# vixen1.net
KiCad netlist of a schematic drawn in EAGLE
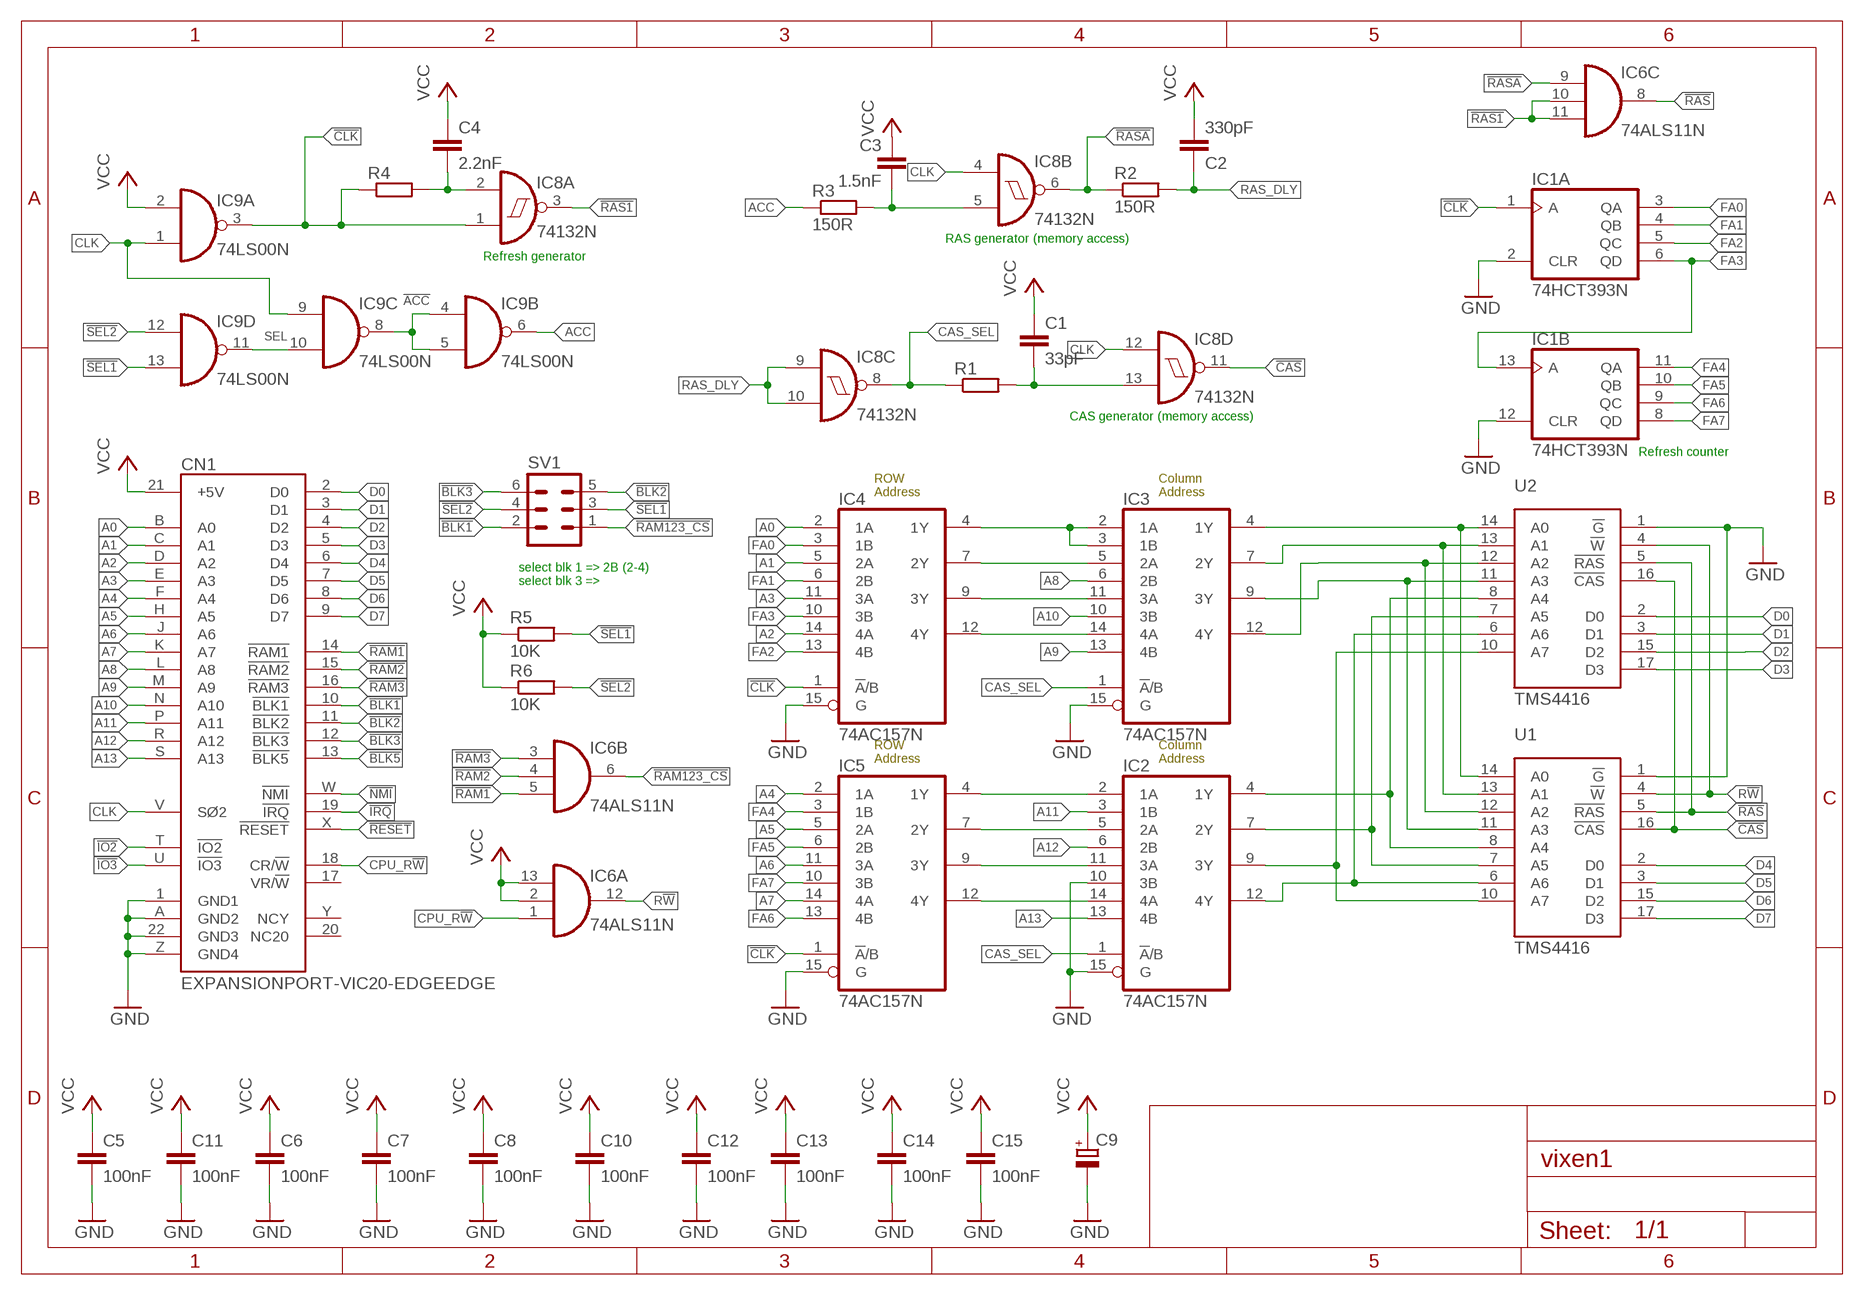
[diagram p0: schematic, sheet 1]

(export (version "E")
  (design (tool "Eeschema 10.0.6"))
  (components
    (comp (ref "C1")
      (value "33pF")
      (footprint "eagle-import:C025-025X050")
      (libsource (lib "eagle-import") (part "C-EU025-025X050"))
    )
    (comp (ref "C2")
      (value "330pF")
      (footprint "eagle-import:C025-025X050")
      (libsource (lib "eagle-import") (part "C-EU025-025X050"))
    )
    (comp (ref "C3")
      (value "1.5nF")
      (footprint "eagle-import:C025-025X050")
      (libsource (lib "eagle-import") (part "C-EU025-025X050"))
    )
    (comp (ref "C4")
      (value "2.2nF")
      (footprint "eagle-import:C025-025X050")
      (libsource (lib "eagle-import") (part "C-EU025-025X050"))
    )
    (comp (ref "C5")
      (value "100nF")
      (footprint "eagle-import:C025-025X050")
      (libsource (lib "eagle-import") (part "C-EU025-025X050"))
    )
    (comp (ref "C6")
      (value "100nF")
      (footprint "eagle-import:C025-025X050")
      (libsource (lib "eagle-import") (part "C-EU025-025X050"))
    )
    (comp (ref "C7")
      (value "100nF")
      (footprint "eagle-import:C025-025X050")
      (libsource (lib "eagle-import") (part "C-EU025-025X050"))
    )
    (comp (ref "C8")
      (value "100nF")
      (footprint "eagle-import:C025-025X050")
      (libsource (lib "eagle-import") (part "C-EU025-025X050"))
    )
    (comp (ref "C9")
      (value "CPOL-EUE15-5AXIAL")
      (footprint "eagle-import:E15-5")
      (libsource (lib "eagle-import") (part "CPOL-EUE15-5AXIAL"))
    )
    (comp (ref "C10")
      (value "100nF")
      (footprint "eagle-import:C025-025X050")
      (libsource (lib "eagle-import") (part "C-EU025-025X050"))
    )
    (comp (ref "C11")
      (value "100nF")
      (footprint "eagle-import:C025-025X050")
      (libsource (lib "eagle-import") (part "C-EU025-025X050"))
    )
    (comp (ref "C12")
      (value "100nF")
      (footprint "eagle-import:C025-025X050")
      (libsource (lib "eagle-import") (part "C-EU025-025X050"))
    )
    (comp (ref "C13")
      (value "100nF")
      (footprint "eagle-import:C025-025X050")
      (libsource (lib "eagle-import") (part "C-EU025-025X050"))
    )
    (comp (ref "C14")
      (value "100nF")
      (footprint "eagle-import:C025-025X050")
      (libsource (lib "eagle-import") (part "C-EU025-025X050"))
    )
    (comp (ref "C15")
      (value "100nF")
      (footprint "eagle-import:C025-025X050")
      (libsource (lib "eagle-import") (part "C-EU025-025X050"))
    )
    (comp (ref "CN1")
      (value "EXPANSIONPORT-VIC20-EDGEEDGE")
      (footprint "eagle-import:UPS44EDGE")
      (libsource (lib "eagle-import") (part "EXPANSIONPORT-VIC20-EDGEEDGE"))
    )
    (comp (ref "IC1")
      (value "74HCT393N")
      (footprint "eagle-import:DIL14")
      (libsource (lib "eagle-import") (part "74393NHCT"))
    )
    (comp (ref "IC2")
      (value "74AC157N")
      (footprint "eagle-import:DIL16")
      (libsource (lib "eagle-import") (part "74157NAC"))
    )
    (comp (ref "IC3")
      (value "74AC157N")
      (footprint "eagle-import:DIL16")
      (libsource (lib "eagle-import") (part "74157NAC"))
    )
    (comp (ref "IC4")
      (value "74AC157N")
      (footprint "eagle-import:DIL16")
      (libsource (lib "eagle-import") (part "74157NAC"))
    )
    (comp (ref "IC5")
      (value "74AC157N")
      (footprint "eagle-import:DIL16")
      (libsource (lib "eagle-import") (part "74157NAC"))
    )
    (comp (ref "IC6")
      (value "74ALS11N")
      (footprint "eagle-import:DIL14")
      (libsource (lib "eagle-import") (part "7411NALS"))
    )
    (comp (ref "IC8")
      (value "74132N")
      (footprint "eagle-import:DIL14")
      (libsource (lib "eagle-import") (part "74132N"))
    )
    (comp (ref "IC9")
      (value "74LS00N")
      (footprint "eagle-import:DIL14")
      (libsource (lib "eagle-import") (part "7400NLS"))
    )
    (comp (ref "R1")
      (value "R-EU_0204/7")
      (footprint "eagle-import:0204_7")
      (libsource (lib "eagle-import") (part "R-EU_0204/7"))
    )
    (comp (ref "R2")
      (value "150R")
      (footprint "eagle-import:0204_7")
      (libsource (lib "eagle-import") (part "R-EU_0204/7"))
    )
    (comp (ref "R3")
      (value "150R")
      (footprint "eagle-import:0204_7")
      (libsource (lib "eagle-import") (part "R-EU_0204/7"))
    )
    (comp (ref "R4")
      (value "R-EU_0204/7")
      (footprint "eagle-import:0204_7")
      (libsource (lib "eagle-import") (part "R-EU_0204/7"))
    )
    (comp (ref "R5")
      (value "10K")
      (footprint "eagle-import:0204_7")
      (libsource (lib "eagle-import") (part "R-EU_0204/7"))
    )
    (comp (ref "R6")
      (value "10K")
      (footprint "eagle-import:0204_7")
      (libsource (lib "eagle-import") (part "R-EU_0204/7"))
    )
    (comp (ref "SV1")
      (value "MA03-2")
      (footprint "eagle-import:MA03-2")
      (libsource (lib "eagle-import") (part "MA03-2"))
    )
    (comp (ref "U1")
      (value "TMS4416")
      (footprint "eagle-import:DIL18")
      (libsource (lib "eagle-import") (part "TMS4416"))
    )
    (comp (ref "U2")
      (value "TMS4416")
      (footprint "eagle-import:DIL18")
      (libsource (lib "eagle-import") (part "TMS4416"))
    )
  )
  (nets
    (net (code "1") (name "/CPU_R~{W}") (class "Default")
      (node (ref "CN1") (pin "18") (pinfunction "CR/~{W}_18") (pintype "output"))
      (node (ref "IC6") (pin "1") (pinfunction "I0_1") (pintype "input"))
    )
    (net (code "2") (name "/R~{W}") (class "Default")
      (node (ref "IC6") (pin "12") (pinfunction "O_12") (pintype "output"))
      (node (ref "U1") (pin "4") (pinfunction "~{W}_4") (pintype "bidirectional"))
      (node (ref "U2") (pin "4") (pinfunction "~{W}_4") (pintype "bidirectional"))
    )
    (net (code "3") (name "/SEL") (class "Default")
      (node (ref "IC9") (pin "10") (pinfunction "I1_10") (pintype "input"))
      (node (ref "IC9") (pin "11") (pinfunction "O_11") (pintype "output"))
    )
    (net (code "4") (name "/~{ACC}") (class "Default")
      (node (ref "IC9") (pin "4") (pinfunction "I0_4") (pintype "input"))
      (node (ref "IC9") (pin "5") (pinfunction "I1_5") (pintype "input"))
      (node (ref "IC9") (pin "8") (pinfunction "O_8") (pintype "output"))
    )
    (net (code "5") (name "/~{BLK1}") (class "Default")
      (node (ref "CN1") (pin "10") (pinfunction "~{BLK1}_10") (pintype "output"))
      (node (ref "SV1") (pin "2") (pinfunction "2_2") (pintype "passive"))
    )
    (net (code "6") (name "/~{BLK2}") (class "Default")
      (node (ref "CN1") (pin "11") (pinfunction "~{BLK2}_11") (pintype "output"))
      (node (ref "SV1") (pin "5") (pinfunction "5_5") (pintype "passive"))
    )
    (net (code "7") (name "/~{BLK3}") (class "Default")
      (node (ref "CN1") (pin "12") (pinfunction "~{BLK3}_12") (pintype "output"))
      (node (ref "SV1") (pin "6") (pinfunction "6_6") (pintype "passive"))
    )
    (net (code "8") (name "/~{BLK5}") (class "Default")
      (node (ref "CN1") (pin "13") (pinfunction "~{BLK5}_13") (pintype "output"))
    )
    (net (code "9") (name "/~{CAS}") (class "Default")
      (node (ref "IC8") (pin "11") (pinfunction "O_11") (pintype "output"))
      (node (ref "U1") (pin "16") (pinfunction "~{CAS}_16") (pintype "bidirectional"))
      (node (ref "U2") (pin "16") (pinfunction "~{CAS}_16") (pintype "bidirectional"))
    )
    (net (code "10") (name "/~{CLK}") (class "Default")
      (node (ref "IC1") (pin "1") (pinfunction "A_1") (pintype "input"))
      (node (ref "IC4") (pin "1") (pinfunction "~{A}/B_1") (pintype "input"))
      (node (ref "IC5") (pin "1") (pinfunction "~{A}/B_1") (pintype "input"))
      (node (ref "IC8") (pin "1") (pinfunction "I0_1") (pintype "input"))
      (node (ref "IC9") (pin "3") (pinfunction "O_3") (pintype "output"))
      (node (ref "R4") (pin "1") (pinfunction "1_1") (pintype "passive"))
    )
    (net (code "11") (name "/~{IO2}") (class "Default")
      (node (ref "CN1") (pin "T") (pinfunction "~{IO2}_T") (pintype "output"))
    )
    (net (code "12") (name "/~{IO3}") (class "Default")
      (node (ref "CN1") (pin "U") (pinfunction "~{IO3}_U") (pintype "output"))
    )
    (net (code "13") (name "/~{IRQ}") (class "Default")
      (node (ref "CN1") (pin "19") (pinfunction "~{IRQ}_19") (pintype "bidirectional"))
    )
    (net (code "14") (name "/~{NMI}") (class "Default")
      (node (ref "CN1") (pin "W") (pinfunction "~{NMI}_W") (pintype "bidirectional"))
    )
    (net (code "15") (name "/~{RAM1}") (class "Default")
      (node (ref "CN1") (pin "14") (pinfunction "~{RAM1}_14") (pintype "output"))
      (node (ref "IC6") (pin "5") (pinfunction "I2_5") (pintype "input"))
    )
    (net (code "16") (name "/~{RAM2}") (class "Default")
      (node (ref "CN1") (pin "15") (pinfunction "~{RAM2}_15") (pintype "output"))
      (node (ref "IC6") (pin "4") (pinfunction "I1_4") (pintype "input"))
    )
    (net (code "17") (name "/~{RAM3}") (class "Default")
      (node (ref "CN1") (pin "16") (pinfunction "~{RAM3}_16") (pintype "output"))
      (node (ref "IC6") (pin "3") (pinfunction "I0_3") (pintype "input"))
    )
    (net (code "18") (name "/~{RAM123_CS}") (class "Default")
      (node (ref "IC6") (pin "6") (pinfunction "O_6") (pintype "output"))
      (node (ref "SV1") (pin "1") (pinfunction "1_1") (pintype "passive"))
    )
    (net (code "19") (name "/~{RAS1}") (class "Default")
      (node (ref "IC6") (pin "10") (pinfunction "I1_10") (pintype "input"))
      (node (ref "IC6") (pin "11") (pinfunction "I2_11") (pintype "input"))
      (node (ref "IC8") (pin "3") (pinfunction "O_3") (pintype "output"))
    )
    (net (code "20") (name "/~{RASA}") (class "Default")
      (node (ref "IC6") (pin "9") (pinfunction "I0_9") (pintype "input"))
      (node (ref "IC8") (pin "6") (pinfunction "O_6") (pintype "output"))
      (node (ref "R2") (pin "1") (pinfunction "1_1") (pintype "passive"))
    )
    (net (code "21") (name "/~{RAS}") (class "Default")
      (node (ref "IC6") (pin "8") (pinfunction "O_8") (pintype "output"))
      (node (ref "U1") (pin "5") (pinfunction "~{RAS}_5") (pintype "bidirectional"))
      (node (ref "U2") (pin "5") (pinfunction "~{RAS}_5") (pintype "bidirectional"))
    )
    (net (code "22") (name "/~{RESET}") (class "Default")
      (node (ref "CN1") (pin "X") (pinfunction "~{RESET}_X") (pintype "bidirectional"))
    )
    (net (code "23") (name "/~{SEL1}") (class "Default")
      (node (ref "IC9") (pin "13") (pinfunction "I1_13") (pintype "input"))
      (node (ref "R5") (pin "2") (pinfunction "2_2") (pintype "passive"))
      (node (ref "SV1") (pin "3") (pinfunction "3_3") (pintype "passive"))
    )
    (net (code "24") (name "/~{SEL2}") (class "Default")
      (node (ref "IC9") (pin "12") (pinfunction "I0_12") (pintype "input"))
      (node (ref "R6") (pin "2") (pinfunction "2_2") (pintype "passive"))
      (node (ref "SV1") (pin "4") (pinfunction "4_4") (pintype "passive"))
    )
    (net (code "25") (name "A0") (class "Default")
      (node (ref "CN1") (pin "B") (pinfunction "A0_B") (pintype "output"))
      (node (ref "IC4") (pin "2") (pinfunction "1A_2") (pintype "input"))
    )
    (net (code "26") (name "A1") (class "Default")
      (node (ref "CN1") (pin "C") (pinfunction "A1_C") (pintype "output"))
      (node (ref "IC4") (pin "5") (pinfunction "2A_5") (pintype "input"))
    )
    (net (code "27") (name "A2") (class "Default")
      (node (ref "CN1") (pin "D") (pinfunction "A2_D") (pintype "output"))
      (node (ref "IC4") (pin "14") (pinfunction "4A_14") (pintype "input"))
    )
    (net (code "28") (name "A3") (class "Default")
      (node (ref "CN1") (pin "E") (pinfunction "A3_E") (pintype "output"))
      (node (ref "IC4") (pin "11") (pinfunction "3A_11") (pintype "input"))
    )
    (net (code "29") (name "A4") (class "Default")
      (node (ref "CN1") (pin "F") (pinfunction "A4_F") (pintype "output"))
      (node (ref "IC5") (pin "2") (pinfunction "1A_2") (pintype "input"))
    )
    (net (code "30") (name "A5") (class "Default")
      (node (ref "CN1") (pin "H") (pinfunction "A5_H") (pintype "output"))
      (node (ref "IC5") (pin "5") (pinfunction "2A_5") (pintype "input"))
    )
    (net (code "31") (name "A6") (class "Default")
      (node (ref "CN1") (pin "J") (pinfunction "A6_J") (pintype "output"))
      (node (ref "IC5") (pin "11") (pinfunction "3A_11") (pintype "input"))
    )
    (net (code "32") (name "A7") (class "Default")
      (node (ref "CN1") (pin "K") (pinfunction "A7_K") (pintype "output"))
      (node (ref "IC5") (pin "14") (pinfunction "4A_14") (pintype "input"))
    )
    (net (code "33") (name "A8") (class "Default")
      (node (ref "CN1") (pin "L") (pinfunction "A8_L") (pintype "output"))
      (node (ref "IC3") (pin "6") (pinfunction "2B_6") (pintype "input"))
    )
    (net (code "34") (name "A9") (class "Default")
      (node (ref "CN1") (pin "M") (pinfunction "A9_M") (pintype "output"))
      (node (ref "IC3") (pin "13") (pinfunction "4B_13") (pintype "input"))
    )
    (net (code "35") (name "A10") (class "Default")
      (node (ref "CN1") (pin "N") (pinfunction "A10_N") (pintype "output"))
      (node (ref "IC3") (pin "10") (pinfunction "3B_10") (pintype "input"))
    )
    (net (code "36") (name "A11") (class "Default")
      (node (ref "CN1") (pin "P") (pinfunction "A11_P") (pintype "output"))
      (node (ref "IC2") (pin "3") (pinfunction "1B_3") (pintype "input"))
    )
    (net (code "37") (name "A12") (class "Default")
      (node (ref "CN1") (pin "R") (pinfunction "A12_R") (pintype "output"))
      (node (ref "IC2") (pin "6") (pinfunction "2B_6") (pintype "input"))
    )
    (net (code "38") (name "A13") (class "Default")
      (node (ref "CN1") (pin "S") (pinfunction "A13_S") (pintype "output"))
      (node (ref "IC2") (pin "13") (pinfunction "4B_13") (pintype "input"))
    )
    (net (code "39") (name "ACC") (class "Default")
      (node (ref "IC9") (pin "6") (pinfunction "O_6") (pintype "output"))
      (node (ref "R3") (pin "1") (pinfunction "1_1") (pintype "passive"))
    )
    (net (code "40") (name "CAS_SEL") (class "Default")
      (node (ref "IC2") (pin "1") (pinfunction "~{A}/B_1") (pintype "input"))
      (node (ref "IC3") (pin "1") (pinfunction "~{A}/B_1") (pintype "input"))
      (node (ref "IC8") (pin "8") (pinfunction "O_8") (pintype "output"))
      (node (ref "R1") (pin "1") (pinfunction "1_1") (pintype "passive"))
    )
    (net (code "41") (name "CLK") (class "Default")
      (node (ref "CN1") (pin "V") (pinfunction "SØ2_V") (pintype "output"))
      (node (ref "IC8") (pin "12") (pinfunction "I0_12") (pintype "input"))
      (node (ref "IC8") (pin "4") (pinfunction "I0_4") (pintype "input"))
      (node (ref "IC9") (pin "1") (pinfunction "I0_1") (pintype "input"))
      (node (ref "IC9") (pin "9") (pinfunction "I0_9") (pintype "input"))
    )
    (net (code "42") (name "D0") (class "Default")
      (node (ref "CN1") (pin "2") (pinfunction "D0_2") (pintype "bidirectional"))
      (node (ref "U2") (pin "2") (pinfunction "D0_2") (pintype "bidirectional"))
    )
    (net (code "43") (name "D1") (class "Default")
      (node (ref "CN1") (pin "3") (pinfunction "D1_3") (pintype "bidirectional"))
      (node (ref "U2") (pin "3") (pinfunction "D1_3") (pintype "bidirectional"))
    )
    (net (code "44") (name "D2") (class "Default")
      (node (ref "CN1") (pin "4") (pinfunction "D2_4") (pintype "bidirectional"))
      (node (ref "U2") (pin "15") (pinfunction "D2_15") (pintype "bidirectional"))
    )
    (net (code "45") (name "D3") (class "Default")
      (node (ref "CN1") (pin "5") (pinfunction "D3_5") (pintype "bidirectional"))
      (node (ref "U2") (pin "17") (pinfunction "D3_17") (pintype "bidirectional"))
    )
    (net (code "46") (name "D4") (class "Default")
      (node (ref "CN1") (pin "6") (pinfunction "D4_6") (pintype "bidirectional"))
      (node (ref "U1") (pin "2") (pinfunction "D0_2") (pintype "bidirectional"))
    )
    (net (code "47") (name "D5") (class "Default")
      (node (ref "CN1") (pin "7") (pinfunction "D5_7") (pintype "bidirectional"))
      (node (ref "U1") (pin "3") (pinfunction "D1_3") (pintype "bidirectional"))
    )
    (net (code "48") (name "D6") (class "Default")
      (node (ref "CN1") (pin "8") (pinfunction "D6_8") (pintype "bidirectional"))
      (node (ref "U1") (pin "15") (pinfunction "D2_15") (pintype "bidirectional"))
    )
    (net (code "49") (name "D7") (class "Default")
      (node (ref "CN1") (pin "9") (pinfunction "D7_9") (pintype "bidirectional"))
      (node (ref "U1") (pin "17") (pinfunction "D3_17") (pintype "bidirectional"))
    )
    (net (code "50") (name "FA0") (class "Default")
      (node (ref "IC1") (pin "3") (pinfunction "QA_3") (pintype "output"))
      (node (ref "IC4") (pin "3") (pinfunction "1B_3") (pintype "input"))
    )
    (net (code "51") (name "FA1") (class "Default")
      (node (ref "IC1") (pin "4") (pinfunction "QB_4") (pintype "output"))
      (node (ref "IC4") (pin "6") (pinfunction "2B_6") (pintype "input"))
    )
    (net (code "52") (name "FA2") (class "Default")
      (node (ref "IC1") (pin "5") (pinfunction "QC_5") (pintype "output"))
      (node (ref "IC4") (pin "13") (pinfunction "4B_13") (pintype "input"))
    )
    (net (code "53") (name "FA3") (class "Default")
      (node (ref "IC1") (pin "13") (pinfunction "A_13") (pintype "input"))
      (node (ref "IC1") (pin "6") (pinfunction "QD_6") (pintype "output"))
      (node (ref "IC4") (pin "10") (pinfunction "3B_10") (pintype "input"))
    )
    (net (code "54") (name "FA4") (class "Default")
      (node (ref "IC1") (pin "11") (pinfunction "QA_11") (pintype "output"))
      (node (ref "IC5") (pin "3") (pinfunction "1B_3") (pintype "input"))
    )
    (net (code "55") (name "FA5") (class "Default")
      (node (ref "IC1") (pin "10") (pinfunction "QB_10") (pintype "output"))
      (node (ref "IC5") (pin "6") (pinfunction "2B_6") (pintype "input"))
    )
    (net (code "56") (name "FA6") (class "Default")
      (node (ref "IC1") (pin "9") (pinfunction "QC_9") (pintype "output"))
      (node (ref "IC5") (pin "13") (pinfunction "4B_13") (pintype "input"))
    )
    (net (code "57") (name "FA7") (class "Default")
      (node (ref "IC1") (pin "8") (pinfunction "QD_8") (pintype "output"))
      (node (ref "IC5") (pin "10") (pinfunction "3B_10") (pintype "input"))
    )
    (net (code "58") (name "GND") (class "Default")
      (node (ref "C10") (pin "2") (pinfunction "2_2") (pintype "passive"))
      (node (ref "C11") (pin "2") (pinfunction "2_2") (pintype "passive"))
      (node (ref "C12") (pin "2") (pinfunction "2_2") (pintype "passive"))
      (node (ref "C13") (pin "2") (pinfunction "2_2") (pintype "passive"))
      (node (ref "C14") (pin "2") (pinfunction "2_2") (pintype "passive"))
      (node (ref "C15") (pin "2") (pinfunction "2_2") (pintype "passive"))
      (node (ref "C5") (pin "2") (pinfunction "2_2") (pintype "passive"))
      (node (ref "C6") (pin "2") (pinfunction "2_2") (pintype "passive"))
      (node (ref "C7") (pin "2") (pinfunction "2_2") (pintype "passive"))
      (node (ref "C8") (pin "2") (pinfunction "2_2") (pintype "passive"))
      (node (ref "C9") (pin "-") (pinfunction "-_-") (pintype "passive"))
      (node (ref "CN1") (pin "1") (pinfunction "GND1_1") (pintype "passive"))
      (node (ref "CN1") (pin "22") (pinfunction "GND3_22") (pintype "passive"))
      (node (ref "CN1") (pin "A") (pinfunction "GND2_A") (pintype "passive"))
      (node (ref "CN1") (pin "Z") (pinfunction "GND4_Z") (pintype "passive"))
      (node (ref "IC1") (pin "12") (pinfunction "CLR_12") (pintype "input"))
      (node (ref "IC1") (pin "2") (pinfunction "CLR_2") (pintype "input"))
      (node (ref "IC2") (pin "10") (pinfunction "3B_10") (pintype "input"))
      (node (ref "IC2") (pin "15") (pinfunction "G_15") (pintype "input"))
      (node (ref "IC3") (pin "15") (pinfunction "G_15") (pintype "input"))
      (node (ref "IC4") (pin "15") (pinfunction "G_15") (pintype "input"))
      (node (ref "IC5") (pin "15") (pinfunction "G_15") (pintype "input"))
      (node (ref "U1") (pin "1") (pinfunction "~{G}_1") (pintype "bidirectional"))
      (node (ref "U2") (pin "1") (pinfunction "~{G}_1") (pintype "bidirectional"))
    )
    (net (code "59") (name "Net-(IC2A-1A)") (class "Default")
      (node (ref "IC2") (pin "2") (pinfunction "1A_2") (pintype "input"))
      (node (ref "IC5") (pin "4") (pinfunction "1Y_4") (pintype "output"))
    )
    (net (code "60") (name "Net-(IC2A-1Y)") (class "Default")
      (node (ref "IC2") (pin "4") (pinfunction "1Y_4") (pintype "output"))
      (node (ref "U1") (pin "8") (pinfunction "A4_8") (pintype "input"))
      (node (ref "U2") (pin "8") (pinfunction "A4_8") (pintype "input"))
    )
    (net (code "61") (name "Net-(IC2A-2A)") (class "Default")
      (node (ref "IC2") (pin "5") (pinfunction "2A_5") (pintype "input"))
      (node (ref "IC5") (pin "7") (pinfunction "2Y_7") (pintype "output"))
    )
    (net (code "62") (name "Net-(IC2A-2Y)") (class "Default")
      (node (ref "IC2") (pin "7") (pinfunction "2Y_7") (pintype "output"))
      (node (ref "U1") (pin "7") (pinfunction "A5_7") (pintype "input"))
      (node (ref "U2") (pin "7") (pinfunction "A5_7") (pintype "input"))
    )
    (net (code "63") (name "Net-(IC2A-3A)") (class "Default")
      (node (ref "IC2") (pin "11") (pinfunction "3A_11") (pintype "input"))
      (node (ref "IC5") (pin "9") (pinfunction "3Y_9") (pintype "output"))
    )
    (net (code "64") (name "Net-(IC2A-3Y)") (class "Default")
      (node (ref "IC2") (pin "9") (pinfunction "3Y_9") (pintype "output"))
      (node (ref "U1") (pin "10") (pinfunction "A7_10") (pintype "input"))
      (node (ref "U2") (pin "10") (pinfunction "A7_10") (pintype "input"))
    )
    (net (code "65") (name "Net-(IC2A-4A)") (class "Default")
      (node (ref "IC2") (pin "14") (pinfunction "4A_14") (pintype "input"))
      (node (ref "IC5") (pin "12") (pinfunction "4Y_12") (pintype "output"))
    )
    (net (code "66") (name "Net-(IC2A-4Y)") (class "Default")
      (node (ref "IC2") (pin "12") (pinfunction "4Y_12") (pintype "output"))
      (node (ref "U1") (pin "6") (pinfunction "A6_6") (pintype "input"))
      (node (ref "U2") (pin "6") (pinfunction "A6_6") (pintype "input"))
    )
    (net (code "67") (name "Net-(IC3A-1A)") (class "Default")
      (node (ref "IC3") (pin "2") (pinfunction "1A_2") (pintype "input"))
      (node (ref "IC3") (pin "3") (pinfunction "1B_3") (pintype "input"))
      (node (ref "IC4") (pin "4") (pinfunction "1Y_4") (pintype "output"))
    )
    (net (code "68") (name "Net-(IC3A-1Y)") (class "Default")
      (node (ref "IC3") (pin "4") (pinfunction "1Y_4") (pintype "output"))
      (node (ref "U1") (pin "14") (pinfunction "A0_14") (pintype "input"))
      (node (ref "U2") (pin "14") (pinfunction "A0_14") (pintype "input"))
    )
    (net (code "69") (name "Net-(IC3A-2A)") (class "Default")
      (node (ref "IC3") (pin "5") (pinfunction "2A_5") (pintype "input"))
      (node (ref "IC4") (pin "7") (pinfunction "2Y_7") (pintype "output"))
    )
    (net (code "70") (name "Net-(IC3A-2Y)") (class "Default")
      (node (ref "IC3") (pin "7") (pinfunction "2Y_7") (pintype "output"))
      (node (ref "U1") (pin "13") (pinfunction "A1_13") (pintype "input"))
      (node (ref "U2") (pin "13") (pinfunction "A1_13") (pintype "input"))
    )
    (net (code "71") (name "Net-(IC3A-3A)") (class "Default")
      (node (ref "IC3") (pin "11") (pinfunction "3A_11") (pintype "input"))
      (node (ref "IC4") (pin "9") (pinfunction "3Y_9") (pintype "output"))
    )
    (net (code "72") (name "Net-(IC3A-3Y)") (class "Default")
      (node (ref "IC3") (pin "9") (pinfunction "3Y_9") (pintype "output"))
      (node (ref "U1") (pin "11") (pinfunction "A3_11") (pintype "input"))
      (node (ref "U2") (pin "11") (pinfunction "A3_11") (pintype "input"))
    )
    (net (code "73") (name "Net-(IC3A-4A)") (class "Default")
      (node (ref "IC3") (pin "14") (pinfunction "4A_14") (pintype "input"))
      (node (ref "IC4") (pin "12") (pinfunction "4Y_12") (pintype "output"))
    )
    (net (code "74") (name "Net-(IC3A-4Y)") (class "Default")
      (node (ref "IC3") (pin "12") (pinfunction "4Y_12") (pintype "output"))
      (node (ref "U1") (pin "12") (pinfunction "A2_12") (pintype "input"))
      (node (ref "U2") (pin "12") (pinfunction "A2_12") (pintype "input"))
    )
    (net (code "75") (name "Net-(IC8A-I1)") (class "Default")
      (node (ref "C4") (pin "2") (pinfunction "2_2") (pintype "passive"))
      (node (ref "IC8") (pin "2") (pinfunction "I1_2") (pintype "input"))
      (node (ref "R4") (pin "2") (pinfunction "2_2") (pintype "passive"))
    )
    (net (code "76") (name "Net-(IC8B-I1)") (class "Default")
      (node (ref "C3") (pin "2") (pinfunction "2_2") (pintype "passive"))
      (node (ref "IC8") (pin "5") (pinfunction "I1_5") (pintype "input"))
      (node (ref "R3") (pin "2") (pinfunction "2_2") (pintype "passive"))
    )
    (net (code "77") (name "Net-(IC8D-I1)") (class "Default")
      (node (ref "C1") (pin "2") (pinfunction "2_2") (pintype "passive"))
      (node (ref "IC8") (pin "13") (pinfunction "I1_13") (pintype "input"))
      (node (ref "R1") (pin "2") (pinfunction "2_2") (pintype "passive"))
    )
    (net (code "78") (name "RAS_DLY") (class "Default")
      (node (ref "C2") (pin "1") (pinfunction "1_1") (pintype "passive"))
      (node (ref "IC8") (pin "10") (pinfunction "I1_10") (pintype "input"))
      (node (ref "IC8") (pin "9") (pinfunction "I0_9") (pintype "input"))
      (node (ref "R2") (pin "2") (pinfunction "2_2") (pintype "passive"))
    )
    (net (code "79") (name "VCC") (class "Default")
      (node (ref "C1") (pin "1") (pinfunction "1_1") (pintype "passive"))
      (node (ref "C10") (pin "1") (pinfunction "1_1") (pintype "passive"))
      (node (ref "C11") (pin "1") (pinfunction "1_1") (pintype "passive"))
      (node (ref "C12") (pin "1") (pinfunction "1_1") (pintype "passive"))
      (node (ref "C13") (pin "1") (pinfunction "1_1") (pintype "passive"))
      (node (ref "C14") (pin "1") (pinfunction "1_1") (pintype "passive"))
      (node (ref "C15") (pin "1") (pinfunction "1_1") (pintype "passive"))
      (node (ref "C2") (pin "2") (pinfunction "2_2") (pintype "passive"))
      (node (ref "C3") (pin "1") (pinfunction "1_1") (pintype "passive"))
      (node (ref "C4") (pin "1") (pinfunction "1_1") (pintype "passive"))
      (node (ref "C5") (pin "1") (pinfunction "1_1") (pintype "passive"))
      (node (ref "C6") (pin "1") (pinfunction "1_1") (pintype "passive"))
      (node (ref "C7") (pin "1") (pinfunction "1_1") (pintype "passive"))
      (node (ref "C8") (pin "1") (pinfunction "1_1") (pintype "passive"))
      (node (ref "C9") (pin "+") (pinfunction "+_+") (pintype "passive"))
      (node (ref "CN1") (pin "21") (pinfunction "+5V_21") (pintype "power_in"))
      (node (ref "IC6") (pin "13") (pinfunction "I2_13") (pintype "input"))
      (node (ref "IC6") (pin "2") (pinfunction "I1_2") (pintype "input"))
      (node (ref "IC9") (pin "2") (pinfunction "I1_2") (pintype "input"))
      (node (ref "R5") (pin "1") (pinfunction "1_1") (pintype "passive"))
      (node (ref "R6") (pin "1") (pinfunction "1_1") (pintype "passive"))
    )
    (net (code "80") (name "unconnected-(CN1-NC20-Pad20)") (class "Default")
      (node (ref "CN1") (pin "20") (pinfunction "NC20_20") (pintype "passive"))
    )
    (net (code "81") (name "unconnected-(CN1-NCY-PadY)") (class "Default")
      (node (ref "CN1") (pin "Y") (pinfunction "NCY_Y") (pintype "passive"))
    )
    (net (code "82") (name "unconnected-(CN1-VR{slash}~{W}-Pad17)") (class "Default")
      (node (ref "CN1") (pin "17") (pinfunction "VR/~{W}_17") (pintype "output"))
    )
  )
)
